# Limit_Switches.net
KiCad netlist of a schematic drawn in Altium Designer
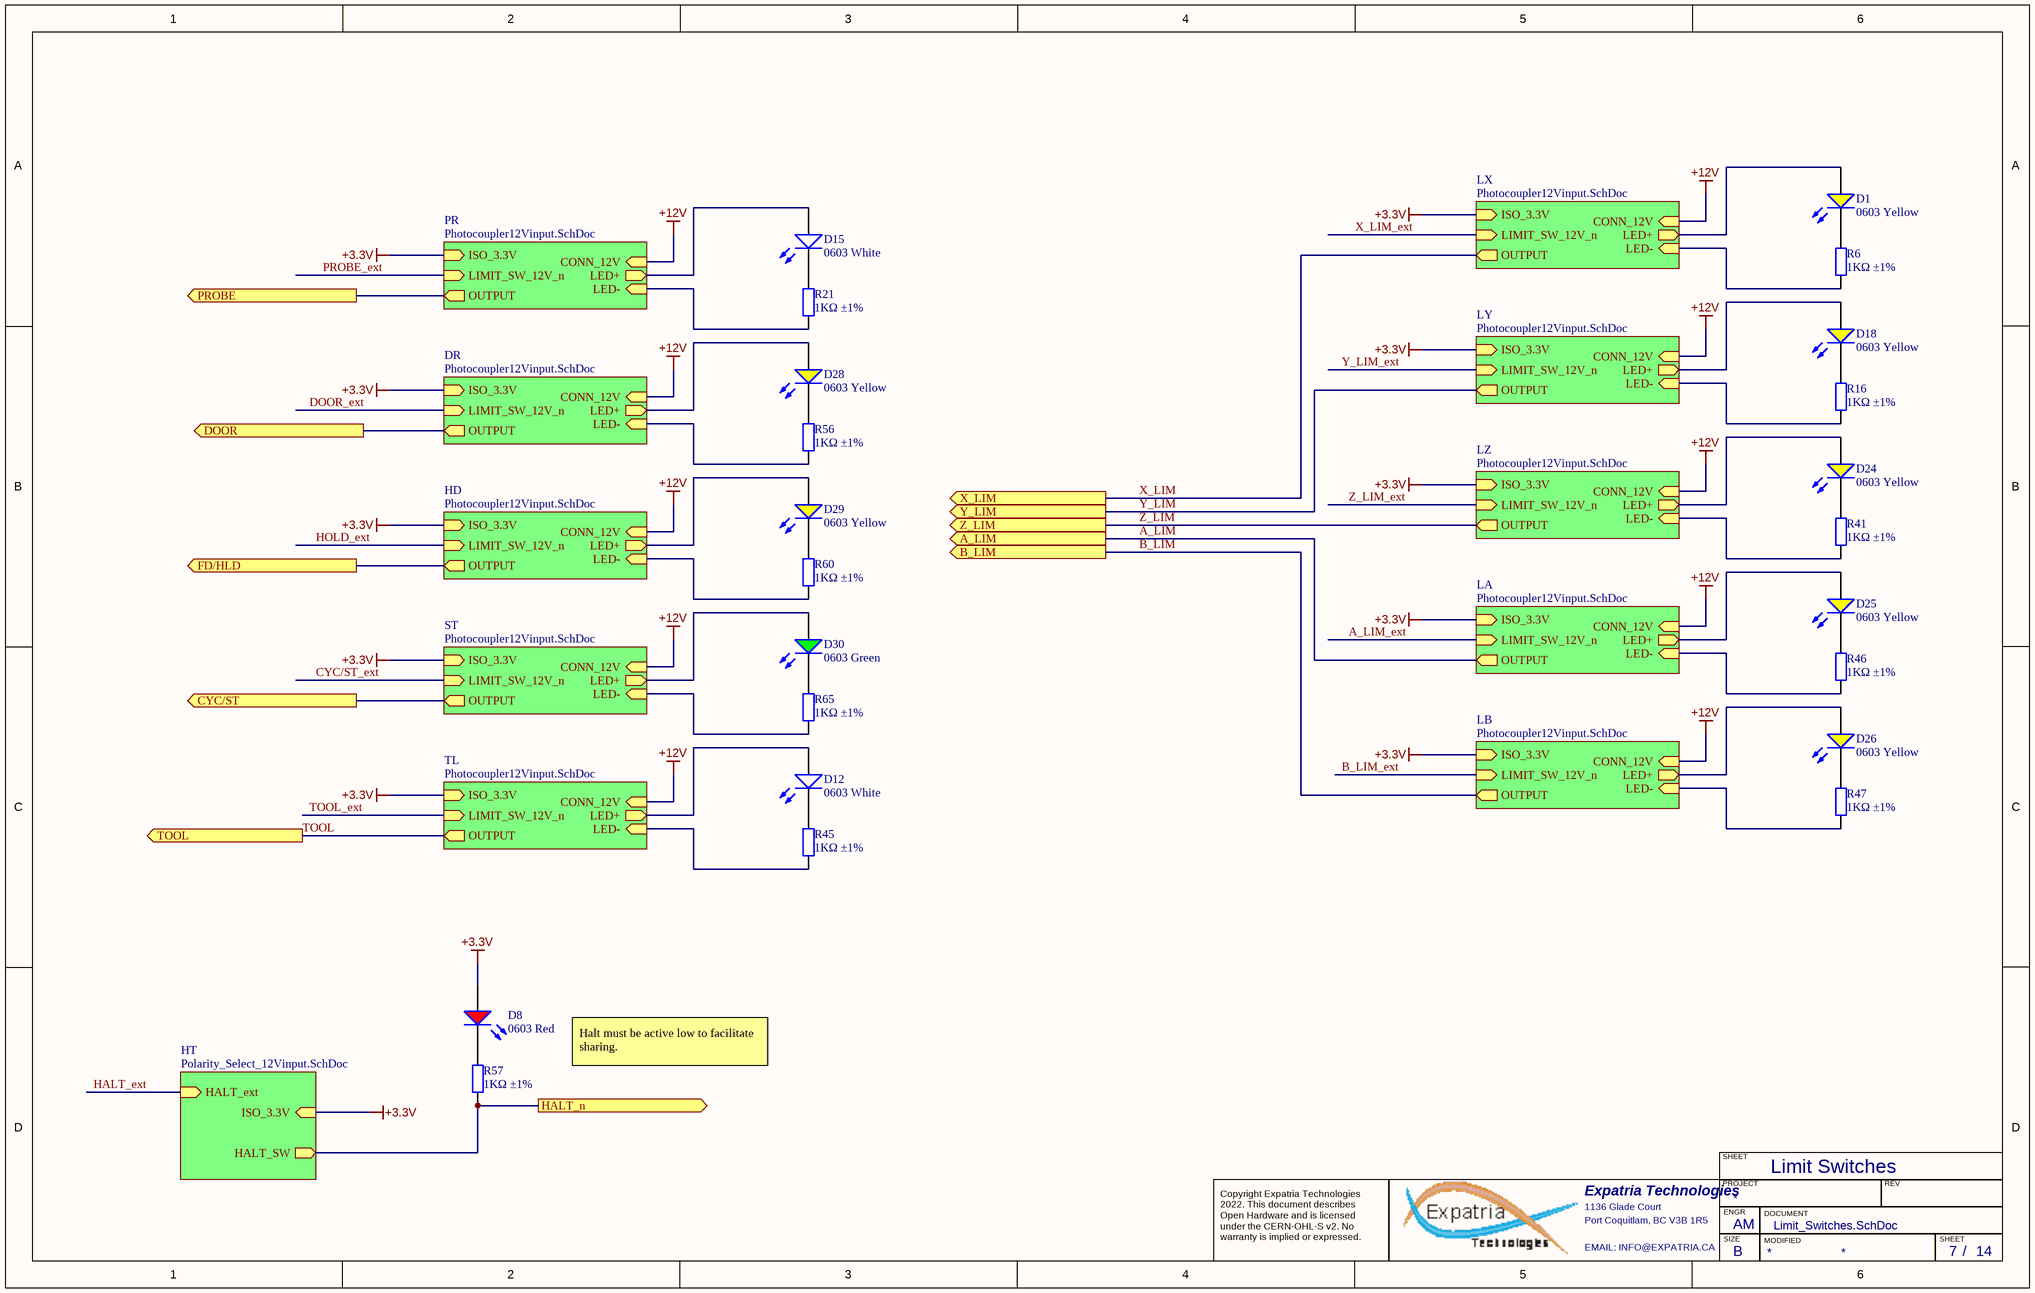
[diagram p0: Limit_Switches.SchDoc]

(export (version "E")
  (design (tool "Eeschema 10.0.6"))
  (components
    (comp (ref "D1")
      (value "0603 Yellow")
      (footprint "0603_LED_S1")
      (description "LED")
      (libsource (lib "LED") (part "0603 LED Yellow"))
    )
    (comp (ref "D8")
      (value "0603 Red")
      (footprint "0603_LED_S1")
      (description "LED")
      (libsource (lib "LED") (part "0603 LED Red"))
    )
    (comp (ref "D12")
      (value "0603 White")
      (footprint "0603_LED_S1")
      (description "LED")
      (libsource (lib "LED") (part "0603 LED White"))
    )
    (comp (ref "D15")
      (value "0603 White")
      (footprint "0603_LED_S1")
      (description "LED")
      (libsource (lib "LED") (part "0603 LED White"))
    )
    (comp (ref "D18")
      (value "0603 Yellow")
      (footprint "0603_LED_S1")
      (description "LED")
      (libsource (lib "LED") (part "0603 LED Yellow"))
    )
    (comp (ref "D24")
      (value "0603 Yellow")
      (footprint "0603_LED_S1")
      (description "LED")
      (libsource (lib "LED") (part "0603 LED Yellow"))
    )
    (comp (ref "D25")
      (value "0603 Yellow")
      (footprint "0603_LED_S1")
      (description "LED")
      (libsource (lib "LED") (part "0603 LED Yellow"))
    )
    (comp (ref "D26")
      (value "0603 Yellow")
      (footprint "0603_LED_S1")
      (description "LED")
      (libsource (lib "LED") (part "0603 LED Yellow"))
    )
    (comp (ref "D28")
      (value "0603 Yellow")
      (footprint "0603_LED_S1")
      (description "LED")
      (libsource (lib "LED") (part "0603 LED Yellow"))
    )
    (comp (ref "D29")
      (value "0603 Yellow")
      (footprint "0603_LED_S1")
      (description "LED")
      (libsource (lib "LED") (part "0603 LED Yellow"))
    )
    (comp (ref "D30")
      (value "0603 Green")
      (footprint "0603_LED_S1")
      (description "LED")
      (libsource (lib "LED") (part "0603 LED Green"))
    )
    (comp (ref "R6")
      (value "1KΩ ±1%")
      (footprint "0402_R")
      (description "Chip resistor")
      (fields (field (name "MANUFACTURER") "Uniroyal Elec") (field (name "PARTNUMBER") "0402WGF1001TCE"))
      (libsource (lib "RES") (part "0402 1K (1001) 1%"))
    )
    (comp (ref "R16")
      (value "1KΩ ±1%")
      (footprint "0402_R")
      (description "Chip resistor")
      (fields (field (name "MANUFACTURER") "Uniroyal Elec") (field (name "PARTNUMBER") "0402WGF1001TCE"))
      (libsource (lib "RES") (part "0402 1K (1001) 1%"))
    )
    (comp (ref "R21")
      (value "1KΩ ±1%")
      (footprint "0402_R")
      (description "Chip resistor")
      (fields (field (name "MANUFACTURER") "Uniroyal Elec") (field (name "PARTNUMBER") "0402WGF1001TCE"))
      (libsource (lib "RES") (part "0402 1K (1001) 1%"))
    )
    (comp (ref "R41")
      (value "1KΩ ±1%")
      (footprint "0402_R")
      (description "Chip resistor")
      (fields (field (name "MANUFACTURER") "Uniroyal Elec") (field (name "PARTNUMBER") "0402WGF1001TCE"))
      (libsource (lib "RES") (part "0402 1K (1001) 1%"))
    )
    (comp (ref "R45")
      (value "1KΩ ±1%")
      (footprint "0402_R")
      (description "Chip resistor")
      (fields (field (name "MANUFACTURER") "Uniroyal Elec") (field (name "PARTNUMBER") "0402WGF1001TCE"))
      (libsource (lib "RES") (part "0402 1K (1001) 1%"))
    )
    (comp (ref "R46")
      (value "1KΩ ±1%")
      (footprint "0402_R")
      (description "Chip resistor")
      (fields (field (name "MANUFACTURER") "Uniroyal Elec") (field (name "PARTNUMBER") "0402WGF1001TCE"))
      (libsource (lib "RES") (part "0402 1K (1001) 1%"))
    )
    (comp (ref "R47")
      (value "1KΩ ±1%")
      (footprint "0402_R")
      (description "Chip resistor")
      (fields (field (name "MANUFACTURER") "Uniroyal Elec") (field (name "PARTNUMBER") "0402WGF1001TCE"))
      (libsource (lib "RES") (part "0402 1K (1001) 1%"))
    )
    (comp (ref "R56")
      (value "1KΩ ±1%")
      (footprint "0402_R")
      (description "Chip resistor")
      (fields (field (name "MANUFACTURER") "Uniroyal Elec") (field (name "PARTNUMBER") "0402WGF1001TCE"))
      (libsource (lib "RES") (part "0402 1K (1001) 1%"))
    )
    (comp (ref "R57")
      (value "1KΩ ±1%")
      (footprint "0402_R")
      (description "Chip resistor")
      (fields (field (name "MANUFACTURER") "Uniroyal Elec") (field (name "PARTNUMBER") "0402WGF1001TCE"))
      (libsource (lib "") (part "0402 1K (1001) 1%_1"))
    )
    (comp (ref "R60")
      (value "1KΩ ±1%")
      (footprint "0402_R")
      (description "Chip resistor")
      (fields (field (name "MANUFACTURER") "Uniroyal Elec") (field (name "PARTNUMBER") "0402WGF1001TCE"))
      (libsource (lib "RES") (part "0402 1K (1001) 1%"))
    )
    (comp (ref "R65")
      (value "1KΩ ±1%")
      (footprint "0402_R")
      (description "Chip resistor")
      (fields (field (name "MANUFACTURER") "Uniroyal Elec") (field (name "PARTNUMBER") "0402WGF1001TCE"))
      (libsource (lib "RES") (part "0402 1K (1001) 1%"))
    )
  )
  (nets
    (net (code "1") (name "+3.3V") (class "Default")
      (node (ref "D8") (pin "A") (pinfunction "A_A") (pintype "passive"))
    )
    (net (code "13") (name "/HALT_n") (class "Default")
      (node (ref "R57") (pin "2") (pinfunction "2_2") (pintype "passive"))
    )
    (net (code "15") (name "/LED+") (class "Default")
      (node (ref "D26") (pin "A") (pinfunction "A_A") (pintype "passive"))
    )
    (net (code "16") (name "/LED+_1") (class "Default")
      (node (ref "D30") (pin "A") (pinfunction "A_A") (pintype "passive"))
    )
    (net (code "17") (name "/LED+_2") (class "Default")
      (node (ref "D12") (pin "A") (pinfunction "A_A") (pintype "passive"))
    )
    (net (code "18") (name "/LED+_3") (class "Default")
      (node (ref "D15") (pin "A") (pinfunction "A_A") (pintype "passive"))
    )
    (net (code "19") (name "/LED+_4") (class "Default")
      (node (ref "D28") (pin "A") (pinfunction "A_A") (pintype "passive"))
    )
    (net (code "20") (name "/LED+_5") (class "Default")
      (node (ref "D29") (pin "A") (pinfunction "A_A") (pintype "passive"))
    )
    (net (code "21") (name "/LED+_6") (class "Default")
      (node (ref "D1") (pin "A") (pinfunction "A_A") (pintype "passive"))
    )
    (net (code "22") (name "/LED+_7") (class "Default")
      (node (ref "D18") (pin "A") (pinfunction "A_A") (pintype "passive"))
    )
    (net (code "23") (name "/LED+_8") (class "Default")
      (node (ref "D24") (pin "A") (pinfunction "A_A") (pintype "passive"))
    )
    (net (code "24") (name "/LED+_9") (class "Default")
      (node (ref "D25") (pin "A") (pinfunction "A_A") (pintype "passive"))
    )
    (net (code "25") (name "/LED-") (class "Default")
      (node (ref "R41") (pin "2") (pinfunction "2_2") (pintype "passive"))
    )
    (net (code "26") (name "/LED-_1") (class "Default")
      (node (ref "R60") (pin "2") (pinfunction "2_2") (pintype "passive"))
    )
    (net (code "27") (name "/LED-_2") (class "Default")
      (node (ref "R65") (pin "2") (pinfunction "2_2") (pintype "passive"))
    )
    (net (code "28") (name "/LED-_3") (class "Default")
      (node (ref "R45") (pin "2") (pinfunction "2_2") (pintype "passive"))
    )
    (net (code "29") (name "/LED-_4") (class "Default")
      (node (ref "R21") (pin "2") (pinfunction "2_2") (pintype "passive"))
    )
    (net (code "30") (name "/LED-_5") (class "Default")
      (node (ref "R56") (pin "2") (pinfunction "2_2") (pintype "passive"))
    )
    (net (code "31") (name "/LED-_6") (class "Default")
      (node (ref "R6") (pin "2") (pinfunction "2_2") (pintype "passive"))
    )
    (net (code "32") (name "/LED-_7") (class "Default")
      (node (ref "R16") (pin "2") (pinfunction "2_2") (pintype "passive"))
    )
    (net (code "33") (name "/LED-_8") (class "Default")
      (node (ref "R46") (pin "2") (pinfunction "2_2") (pintype "passive"))
    )
    (net (code "34") (name "/LED-_9") (class "Default")
      (node (ref "R47") (pin "2") (pinfunction "2_2") (pintype "passive"))
    )
    (net (code "45") (name "Net-(D1-PadK)") (class "Default")
      (node (ref "D1") (pin "K") (pinfunction "K_K") (pintype "passive"))
      (node (ref "R6") (pin "1") (pinfunction "1_1") (pintype "passive"))
    )
    (net (code "46") (name "Net-(D8-PadK)") (class "Default")
      (node (ref "D8") (pin "K") (pinfunction "K_K") (pintype "passive"))
      (node (ref "R57") (pin "1") (pinfunction "1_1") (pintype "passive"))
    )
    (net (code "47") (name "Net-(D12-PadK)") (class "Default")
      (node (ref "D12") (pin "K") (pinfunction "K_K") (pintype "passive"))
      (node (ref "R45") (pin "1") (pinfunction "1_1") (pintype "passive"))
    )
    (net (code "48") (name "Net-(D15-PadK)") (class "Default")
      (node (ref "D15") (pin "K") (pinfunction "K_K") (pintype "passive"))
      (node (ref "R21") (pin "1") (pinfunction "1_1") (pintype "passive"))
    )
    (net (code "49") (name "Net-(D18-PadK)") (class "Default")
      (node (ref "D18") (pin "K") (pinfunction "K_K") (pintype "passive"))
      (node (ref "R16") (pin "1") (pinfunction "1_1") (pintype "passive"))
    )
    (net (code "50") (name "Net-(D24-PadK)") (class "Default")
      (node (ref "D24") (pin "K") (pinfunction "K_K") (pintype "passive"))
      (node (ref "R41") (pin "1") (pinfunction "1_1") (pintype "passive"))
    )
    (net (code "51") (name "Net-(D25-PadK)") (class "Default")
      (node (ref "D25") (pin "K") (pinfunction "K_K") (pintype "passive"))
      (node (ref "R46") (pin "1") (pinfunction "1_1") (pintype "passive"))
    )
    (net (code "52") (name "Net-(D26-PadK)") (class "Default")
      (node (ref "D26") (pin "K") (pinfunction "K_K") (pintype "passive"))
      (node (ref "R47") (pin "1") (pinfunction "1_1") (pintype "passive"))
    )
    (net (code "53") (name "Net-(D28-PadK)") (class "Default")
      (node (ref "D28") (pin "K") (pinfunction "K_K") (pintype "passive"))
      (node (ref "R56") (pin "1") (pinfunction "1_1") (pintype "passive"))
    )
    (net (code "54") (name "Net-(D29-PadK)") (class "Default")
      (node (ref "D29") (pin "K") (pinfunction "K_K") (pintype "passive"))
      (node (ref "R60") (pin "1") (pinfunction "1_1") (pintype "passive"))
    )
    (net (code "55") (name "Net-(D30-PadK)") (class "Default")
      (node (ref "D30") (pin "K") (pinfunction "K_K") (pintype "passive"))
      (node (ref "R65") (pin "1") (pinfunction "1_1") (pintype "passive"))
    )
  )
)
